# Input_Digital.net
KiCad netlist of a schematic drawn in Altium Designer
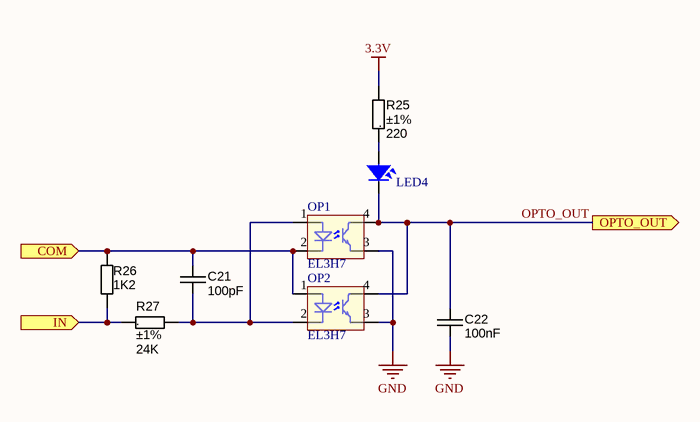
[diagram p0: Input Digital.SchDoc]

(export (version "E")
  (design (tool "Eeschema 10.0.6"))
  (components
    (comp (ref "C21")
      (value "100pF")
      (footprint "CAPC1608X90N")
      (description "100pF ±5% 100V Ceramic Capacitor C0G, NP0 0603 (1608 Metric)")
      (fields (field (name "TOLERANCE") "±5%"))
      (libsource (lib "SangMV") (part "CAPC_100pF_0603_C0G_NP0_100V_5%"))
    )
    (comp (ref "C22")
      (value "100nF")
      (footprint "CAPC1608X90N")
      (description "0.1µF ±10% 50V Ceramic Capacitor X7R 0603 (1608 Metric)")
      (fields (field (name "TOLERANCE") "±10%"))
      (libsource (lib "All Library") (part "CAPC_100nF_0603_X7R_50V_10%"))
    )
    (comp (ref "LED4")
      (value "LED")
      (footprint "LED-0805-Green")
      (libsource (lib "thu vien 3d") (part "LED SMD"))
    )
    (comp (ref "OP1")
      (value "EL3H7")
      (footprint "IC_SMD_SSOP4_NEW")
      (description "Photo Transistor")
      (libsource (lib "All Library") (part "OPTO_EL3H7"))
    )
    (comp (ref "OP2")
      (value "EL3H7")
      (footprint "IC_SMD_SSOP4_NEW")
      (description "Photo Transistor")
      (libsource (lib "All Library") (part "OPTO_EL3H7"))
    )
    (comp (ref "R25")
      (value "220")
      (footprint "RESC1608X55N")
      (fields
        (field (name "MANUFACTURER") "Stackpole Electronics Inc")
        (field (name "MANUFACTURER PART NUMBER") "RMCF0603FT10K0")
        (field (name "TOLERANCE") "±1%")
        (field (name "Comment") "10K_0603_1%")
      )
      (libsource (lib "All Library") (part "RES_10K_0603_1%"))
    )
    (comp (ref "R26")
      (value "1K2")
      (footprint "RES_2W_AXIAL_11x4_STAND")
      (description "Resistor THD 390 Ohm 2W 5% Metal Film")
      (fields (field (name "TOLERANCE") "±5%") (field (name "Comment") "Metal Film"))
      (libsource (lib "All Library") (part "RES_390R_Axial_2W_5%"))
    )
    (comp (ref "R27")
      (value "24K")
      (footprint "RESC2012X70N")
      (description "24 kOhms ±1% 0.125W, 1/8W Chip Resistor 0805 (2012 Metric) Automotive AEC-Q200 Thick Film")
      (fields
        (field (name "MANUFACTURER") "Stackpole Electronics Inc")
        (field (name "MANUFACTURER PART NUMBER") "RMCF0805FT10K5")
        (field (name "TOLERANCE") "±1%")
      )
      (libsource (lib "All Library") (part "RES_24K_0805_1%"))
    )
  )
  (nets
    (net (code "1") (name "/COM") (class "Default")
      (node (ref "C21") (pin "1") (pintype "passive"))
      (node (ref "OP1") (pin "2") (pinfunction "K_2") (pintype "passive"))
      (node (ref "OP2") (pin "1") (pinfunction "A_1") (pintype "passive"))
      (node (ref "R26") (pin "1") (pinfunction "1_1") (pintype "passive"))
    )
    (net (code "2") (name "/IN") (class "Default")
      (node (ref "R26") (pin "2") (pinfunction "2_2") (pintype "passive"))
      (node (ref "R27") (pin "1") (pinfunction "1_1") (pintype "passive"))
    )
    (net (code "3") (name "/OPTO_OUT") (class "Default")
      (node (ref "C22") (pin "1") (pintype "passive"))
      (node (ref "LED4") (pin "2") (pinfunction "2_2") (pintype "passive"))
      (node (ref "OP1") (pin "4") (pinfunction "C_4") (pintype "passive"))
      (node (ref "OP2") (pin "4") (pinfunction "C_4") (pintype "passive"))
    )
    (net (code "4") (name "3.3V") (class "Default")
      (node (ref "R25") (pin "2") (pinfunction "2_2") (pintype "passive"))
    )
    (net (code "5") (name "GND") (class "Default")
      (node (ref "C22") (pin "2") (pintype "passive"))
      (node (ref "OP1") (pin "3") (pinfunction "E_3") (pintype "passive"))
      (node (ref "OP2") (pin "3") (pinfunction "E_3") (pintype "passive"))
    )
    (net (code "6") (name "Net-(LED4-Pad1)") (class "Default")
      (node (ref "LED4") (pin "1") (pinfunction "1_1") (pintype "passive"))
      (node (ref "R25") (pin "1") (pinfunction "1_1") (pintype "passive"))
    )
    (net (code "7") (name "Net-(OP1-A)") (class "Default")
      (node (ref "C21") (pin "2") (pintype "passive"))
      (node (ref "OP1") (pin "1") (pinfunction "A_1") (pintype "passive"))
      (node (ref "OP2") (pin "2") (pinfunction "K_2") (pintype "passive"))
      (node (ref "R27") (pin "2") (pinfunction "2_2") (pintype "passive"))
    )
  )
)
